# LINEARDriver_DC.net
KiCad netlist of a schematic drawn in Altium Designer
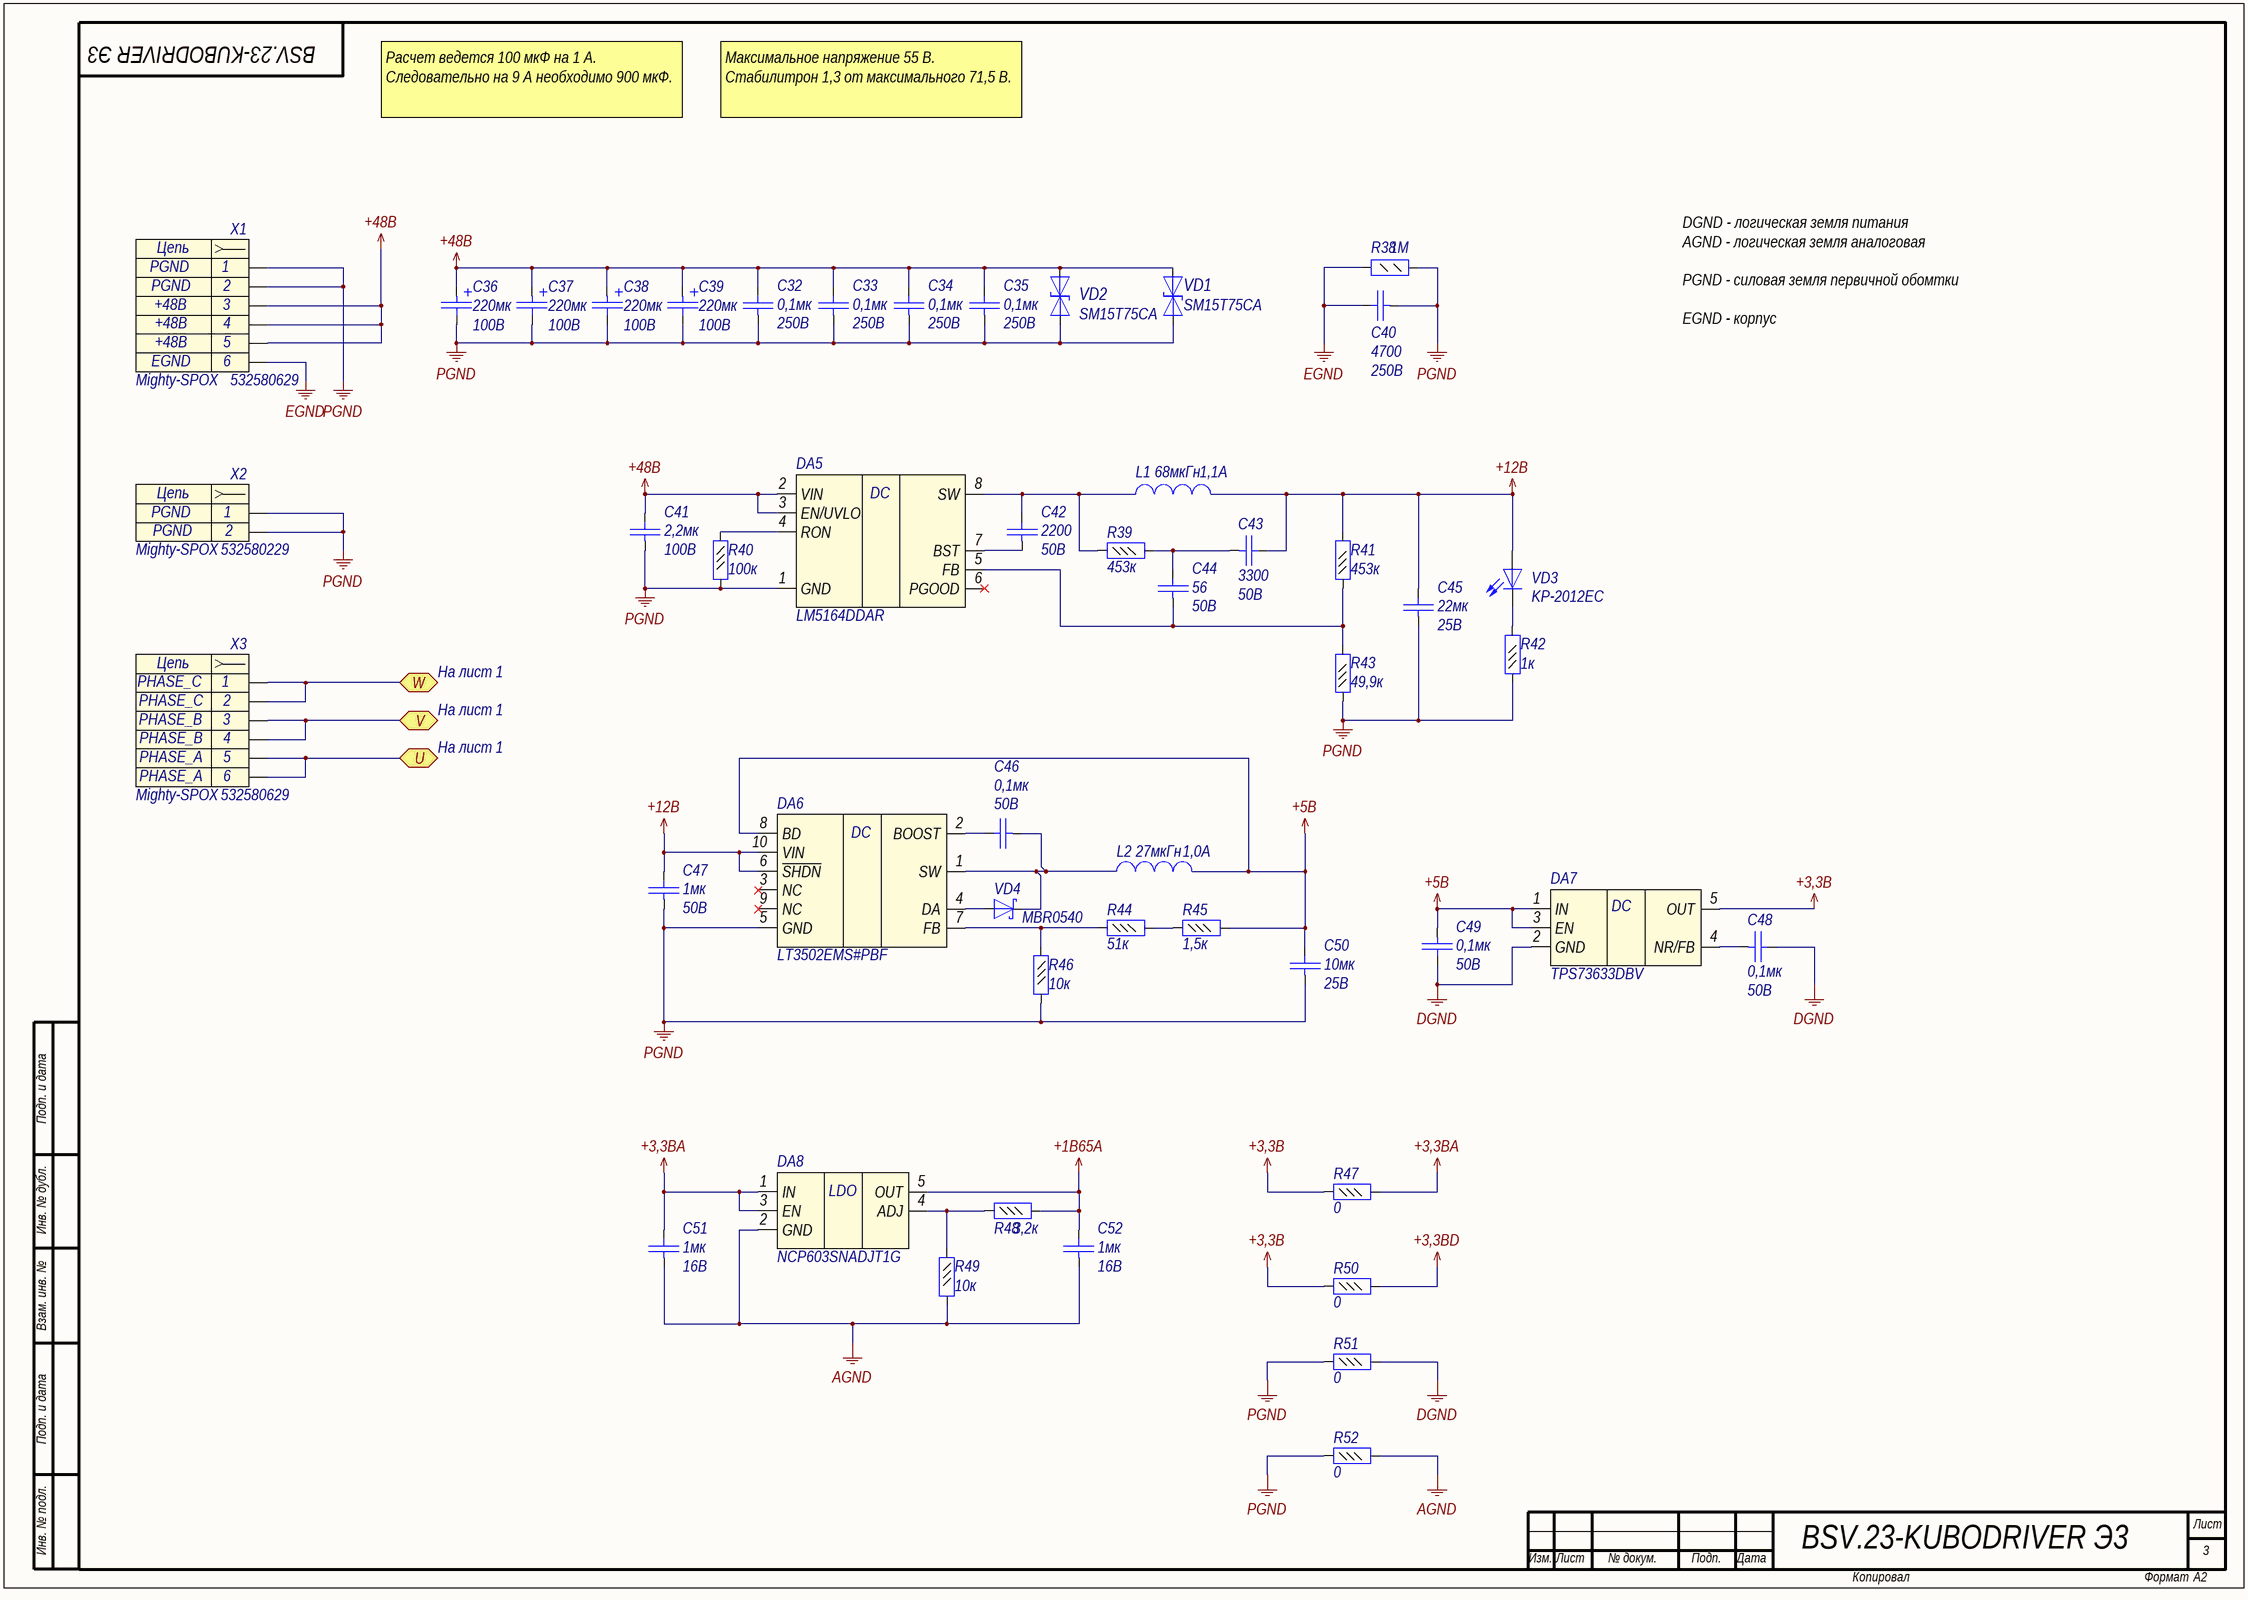
[diagram p0: LINEARDriver_DC.SchDoc]

(export (version "E")
  (design (tool "Eeschema 10.0.6"))
  (components
    (comp (ref "C32")
      (value "0,1мк")
      (footprint "C1206")
      (description "Конденсатор")
      (fields
        (field (name "VOLTAGE") "250В")
        (field (name "PART NUMBER") "GRM31CR72E104K")
        (field (name "Comment") "Capacitor")
      )
      (libsource (lib "MOP44") (part "Capacitor"))
    )
    (comp (ref "C33")
      (value "0,1мк")
      (footprint "C1206")
      (description "Конденсатор")
      (fields
        (field (name "VOLTAGE") "250В")
        (field (name "PART NUMBER") "GRM31CR72E104K")
        (field (name "Comment") "Capacitor")
      )
      (libsource (lib "MOP44") (part "Capacitor"))
    )
    (comp (ref "C34")
      (value "0,1мк")
      (footprint "C1206")
      (description "Конденсатор")
      (fields
        (field (name "VOLTAGE") "250В")
        (field (name "PART NUMBER") "GRM31CR72E104K")
        (field (name "Comment") "Capacitor")
      )
      (libsource (lib "MOP44") (part "Capacitor"))
    )
    (comp (ref "C35")
      (value "0,1мк")
      (footprint "C1206")
      (description "Конденсатор")
      (fields
        (field (name "VOLTAGE") "250В")
        (field (name "PART NUMBER") "GRM31CR72E104K")
        (field (name "Comment") "Capacitor")
      )
      (libsource (lib "MOP44") (part "Capacitor"))
    )
    (comp (ref "C36")
      (value "220мк")
      (footprint "K50-35(12.5X25)_V")
      (description "Конденсатор полярный")
      (fields
        (field (name "VOLTAGE") "100B")
        (field (name "PART NUMBER") "B41851A9227M000")
        (field (name "Comment") "Capacitor_pol")
      )
      (libsource (lib "MOP44") (part "Capacitor_pol"))
    )
    (comp (ref "C37")
      (value "220мк")
      (footprint "K50-35(12.5X25)_V")
      (description "Конденсатор полярный")
      (fields
        (field (name "VOLTAGE") "100B")
        (field (name "PART NUMBER") "B41851A9227M000")
        (field (name "Comment") "Capacitor_pol")
      )
      (libsource (lib "MOP44") (part "Capacitor_pol"))
    )
    (comp (ref "C38")
      (value "220мк")
      (footprint "K50-35(12.5X25)_V")
      (description "Конденсатор полярный")
      (fields
        (field (name "VOLTAGE") "100B")
        (field (name "PART NUMBER") "B41851A9227M000")
        (field (name "Comment") "Capacitor_pol")
      )
      (libsource (lib "MOP44") (part "Capacitor_pol"))
    )
    (comp (ref "C39")
      (value "220мк")
      (footprint "K50-35(12.5X25)_V")
      (description "Конденсатор полярный")
      (fields
        (field (name "VOLTAGE") "100B")
        (field (name "PART NUMBER") "B41851A9227M000")
        (field (name "Comment") "Capacitor_pol")
      )
      (libsource (lib "MOP44") (part "Capacitor_pol"))
    )
    (comp (ref "C40")
      (value "4700")
      (footprint "C0805")
      (description "Конденсатор")
      (fields
        (field (name "VOLTAGE") "250В")
        (field (name "PART NUMBER") "GRM21AR72E472KW")
        (field (name "Comment") "Capacitor")
      )
      (libsource (lib "MOP44") (part "Capacitor"))
    )
    (comp (ref "C41")
      (value "2,2мк")
      (footprint "C1210")
      (description "Конденсатор")
      (fields (field (name "VOLTAGE") "100В") (field (name "PART NUMBER") "GCJ32DR72A225KA01L"))
      (libsource (lib "MOP44") (part "Capacitor"))
    )
    (comp (ref "C42")
      (value "2200")
      (footprint "C0402")
      (description "Конденсатор")
      (fields
        (field (name "VOLTAGE") "50B")
        (field (name "PART NUMBER") "GRM155R71H222K")
        (field (name "Comment") "Capacitor")
      )
      (libsource (lib "MOP44") (part "Capacitor"))
    )
    (comp (ref "C43")
      (value "3300")
      (footprint "C0402")
      (description "Конденсатор")
      (fields
        (field (name "VOLTAGE") "50В")
        (field (name "PART NUMBER") "GRM155R71H332KA01D ")
        (field (name "Comment") "Capacitor")
      )
      (libsource (lib "MOP44") (part "Capacitor"))
    )
    (comp (ref "C44")
      (value "56")
      (footprint "C0402")
      (description "Конденсатор")
      (fields
        (field (name "VOLTAGE") "50B")
        (field (name "PART NUMBER") "GRM1555C1H560J*")
        (field (name "Comment") "Capacitor")
      )
      (libsource (lib "MOP44") (part "Capacitor"))
    )
    (comp (ref "C45")
      (value "22мк")
      (footprint "C1210")
      (description "Конденсатор")
      (fields
        (field (name "VOLTAGE") "25B")
        (field (name "PART NUMBER") "TMK325B7226KMHT")
        (field (name "Comment") "Capacitor")
      )
      (libsource (lib "MOP44") (part "Capacitor"))
    )
    (comp (ref "C46")
      (value "0,1мк")
      (footprint "C0402")
      (description "Конденсатор")
      (fields
        (field (name "VOLTAGE") "50В")
        (field (name "PART NUMBER") "GRM155R71H104KE14D ")
        (field (name "Comment") "Capacitor")
      )
      (libsource (lib "MOP44") (part "Capacitor"))
    )
    (comp (ref "C47")
      (value "1мк")
      (footprint "C0805")
      (description "Конденсатор")
      (fields
        (field (name "VOLTAGE") "50B")
        (field (name "PART NUMBER") "GRM21BR71H105K")
        (field (name "Comment") "Capacitor")
      )
      (libsource (lib "MOP44") (part "Capacitor"))
    )
    (comp (ref "C48")
      (value "0,1мк")
      (footprint "C0402")
      (description "Конденсатор")
      (fields
        (field (name "VOLTAGE") "50В")
        (field (name "PART NUMBER") "GRM155R71H104KE14D ")
        (field (name "Comment") "Capacitor")
      )
      (libsource (lib "MOP44") (part "Capacitor"))
    )
    (comp (ref "C49")
      (value "0,1мк")
      (footprint "C0402")
      (description "Конденсатор")
      (fields
        (field (name "VOLTAGE") "50В")
        (field (name "PART NUMBER") "GRM155R71H104KE14D ")
        (field (name "Comment") "Capacitor")
      )
      (libsource (lib "MOP44") (part "Capacitor"))
    )
    (comp (ref "C50")
      (value "10мк")
      (footprint "C1206")
      (description "Конденсатор")
      (fields
        (field (name "VOLTAGE") "25В")
        (field (name "PART NUMBER") "GRM31CR71E106KA12L*")
        (field (name "Comment") "Capacitor")
      )
      (libsource (lib "MOP44") (part "Capacitor"))
    )
    (comp (ref "C51")
      (value "1мк")
      (footprint "C0603")
      (description "Конденсатор")
      (fields
        (field (name "VOLTAGE") "16B")
        (field (name "PART NUMBER") "GRM188R71C105KA12D**")
        (field (name "Comment") "Capacitor")
      )
      (libsource (lib "MOP44") (part "Capacitor"))
    )
    (comp (ref "C52")
      (value "1мк")
      (footprint "C0603")
      (description "Конденсатор")
      (fields
        (field (name "VOLTAGE") "16B")
        (field (name "PART NUMBER") "GRM188R71C105KA12D**")
        (field (name "Comment") "Capacitor")
      )
      (libsource (lib "MOP44") (part "Capacitor"))
    )
    (comp (ref "DA5")
      (value "LM5164")
      (footprint "SO Powerpad8")
      (description "1-A synchronous buck DC/DC converter with ultra-low IQ")
      (fields (field (name "PART NUMBER") "LM5164DDAR") (field (name "MANUFACTURER") "Texas Instruments"))
      (libsource (lib "MOP44") (part "LM5164"))
    )
    (comp (ref "DA6")
      (value "LT3502_MS")
      (footprint "MSOP10")
      (description "1.1MHz/2.2MHz, 500mA  Step-Down Regulators")
      (fields (field (name "PART NUMBER") "LT3502EMS#PBF") (field (name "MANUFACTURER") "Linear Technology"))
      (libsource (lib "MOP44") (part "LT3502_MS"))
    )
    (comp (ref "DA7")
      (value "TPS736DBV")
      (footprint "SOT23-5")
      (description "400-mA Low-Dropout Regulator with Reverse Current  Protection")
      (fields (field (name "PART NUMBER") "TPS73633DBV") (field (name "MANUFACTURER") "Texas Instruments"))
      (libsource (lib "MOP44") (part "TPS736DBV"))
    )
    (comp (ref "DA8")
      (value "NCP603")
      (footprint "TSOP5")
      (description "High Performance  CMOS LDO Regulator with  Enable and Enhanced ESD  Protection")
      (fields (field (name "PART NUMBER") "NCP603SNADJT1G") (field (name "MANUFACTURER") "ON Semiconductor"))
      (libsource (lib "MOP44") (part "NCP603"))
    )
    (comp (ref "L1")
      (value "68мкГн")
      (footprint "SDR1006")
      (description "EMI Suppression Filter")
      (fields
        (field (name "RATED CURRENT") "1,1A")
        (field (name "PART NUMBER") "SDR1006- 680KL")
        (field (name "Comment") "Inductor")
      )
      (libsource (lib "MOP44") (part "Inductor"))
    )
    (comp (ref "L2")
      (value "27мкГн")
      (footprint "SDR0604")
      (description "EMI Suppression Filter")
      (fields
        (field (name "RATED CURRENT") "1,0A")
        (field (name "PART NUMBER") "SDR0604- 270YL")
        (field (name "Comment") "Inductor")
      )
      (libsource (lib "MOP44") (part "Inductor"))
    )
    (comp (ref "R38")
      (value "1М")
      (footprint "R0805")
      (description "Резистор")
      (fields (field (name "PART NUMBER") "RC0805FR-071ML") (field (name "POWER") "0,125Вт"))
      (libsource (lib "MOP44") (part "Resistor_0,125Вт"))
    )
    (comp (ref "R39")
      (value "453к")
      (footprint "R0402")
      (description "Резистор")
      (fields (field (name "PART NUMBER") "RC0402FR-07453KL") (field (name "POWER") "0,062Вт"))
      (libsource (lib "") (part "Resistor_0,062Вт_1"))
    )
    (comp (ref "R40")
      (value "100к")
      (footprint "R0402")
      (description "Резистор")
      (fields (field (name "PART NUMBER") "RC0402FR-07100KL") (field (name "POWER") "0,062Вт"))
      (libsource (lib "") (part "Resistor_0,062Вт_2"))
    )
    (comp (ref "R41")
      (value "453к")
      (footprint "R0402")
      (description "Резистор")
      (fields (field (name "PART NUMBER") "RC0402FR-07453KL") (field (name "POWER") "0,062Вт"))
      (libsource (lib "MOP44") (part "Resistor_0,062Вт"))
    )
    (comp (ref "R42")
      (value "1к")
      (footprint "R0402")
      (description "Резистор")
      (fields (field (name "PART NUMBER") "RC0402FR-071KL") (field (name "POWER") "0,062Вт"))
      (libsource (lib "MOP44") (part "Resistor_0,062Вт"))
    )
    (comp (ref "R43")
      (value "49,9к")
      (footprint "R0402")
      (description "Резистор")
      (fields (field (name "PART NUMBER") "RC0402FR-0749K9L") (field (name "POWER") "0,062Вт"))
      (libsource (lib "MOP44") (part "Resistor_0,062Вт"))
    )
    (comp (ref "R44")
      (value "51к")
      (footprint "R0402")
      (description "Резистор")
      (fields (field (name "PART NUMBER") "RC0402FR-0751KL") (field (name "POWER") "0,062Вт"))
      (libsource (lib "") (part "Resistor_0,062Вт_1"))
    )
    (comp (ref "R45")
      (value "1,5к")
      (footprint "R0402")
      (description "Резистор")
      (fields (field (name "PART NUMBER") "RC0402FR-071K5") (field (name "POWER") "0,062Вт"))
      (libsource (lib "") (part "Resistor_0,062Вт_1"))
    )
    (comp (ref "R46")
      (value "10к")
      (footprint "R0402")
      (description "Резистор")
      (fields (field (name "PART NUMBER") "RC0402FR-0710KL") (field (name "POWER") "0,062Вт"))
      (libsource (lib "") (part "Resistor_0,062Вт_2"))
    )
    (comp (ref "R47")
      (value "0")
      (footprint "R0603")
      (description "Резистор")
      (fields (field (name "PART NUMBER") "RC0603FR-070RL") (field (name "POWER") "0,062Вт"))
      (libsource (lib "") (part "Resistor_0,062Вт_1"))
    )
    (comp (ref "R48")
      (value "3,2к")
      (footprint "R0402")
      (description "Резистор")
      (fields (field (name "PART NUMBER") "RT0402BRD073K2L") (field (name "POWER") "0,062Вт"))
      (libsource (lib "") (part "Resistor_0,062Вт_1"))
    )
    (comp (ref "R49")
      (value "10к")
      (footprint "R0402")
      (description "Резистор")
      (fields (field (name "PART NUMBER") "RC0402FR-0710KL") (field (name "POWER") "0,062Вт"))
      (libsource (lib "") (part "Resistor_0,062Вт_2"))
    )
    (comp (ref "R50")
      (value "0")
      (footprint "R0603")
      (description "Резистор")
      (fields (field (name "PART NUMBER") "RC0603FR-070RL") (field (name "POWER") "0,062Вт"))
      (libsource (lib "") (part "Resistor_0,062Вт_1"))
    )
    (comp (ref "R51")
      (value "0")
      (footprint "R0603")
      (description "Резистор")
      (fields (field (name "PART NUMBER") "RC0603FR-070RL") (field (name "POWER") "0,062Вт"))
      (libsource (lib "") (part "Resistor_0,062Вт_1"))
    )
    (comp (ref "R52")
      (value "0")
      (footprint "R0603")
      (description "Резистор")
      (fields (field (name "PART NUMBER") "RC0603FR-070RL") (field (name "POWER") "0,062Вт"))
      (libsource (lib "") (part "Resistor_0,062Вт_1"))
    )
    (comp (ref "VD1")
      (value "DiodeZenerDual")
      (footprint "SMC")
      (description "Cтабилитрон (диод выпрямительный лавинный) двусторонний")
      (fields (field (name "PART NUMBER") "SM15T75CA"))
      (libsource (lib "MOP44") (part "DiodeZenerDual"))
    )
    (comp (ref "VD2")
      (value "DiodeZenerDual")
      (footprint "SMC")
      (description "Cтабилитрон (диод выпрямительный лавинный) двусторонний")
      (fields (field (name "PART NUMBER") "SM15T75CA"))
      (libsource (lib "MOP44") (part "DiodeZenerDual"))
    )
    (comp (ref "VD3")
      (value "LED")
      (footprint "L_0805")
      (description "Светодиод")
      (fields (field (name "PART NUMBER") "KP-2012EC"))
      (libsource (lib "MOP44") (part "LED"))
    )
    (comp (ref "VD4")
      (value "DiodeSchottky")
      (footprint "SOD-123")
      (description "Диод Шоттки")
      (fields (field (name "PART NUMBER") "MBR0540"))
      (libsource (lib "MOP44") (part "DiodeSchottky"))
    )
    (comp (ref "X1")
      (value "Header_6_sct")
      (footprint "MOLEX_532580629")
      (description "Разъем - 6 конт. розетка")
      (fields (field (name "PART NAME") "Mighty-SPOX") (field (name "PART NUMBER") "532580629"))
      (libsource (lib "MOP44") (part "Header_6_sct"))
    )
    (comp (ref "X2")
      (value "Header_2_sct")
      (footprint "MOLEX_532580229")
      (description "Разъем - 2 конт. розетка")
      (fields (field (name "PART NAME") "Mighty-SPOX") (field (name "PART NUMBER") "532580229"))
      (libsource (lib "MOP44") (part "Header_2_sct"))
    )
    (comp (ref "X3")
      (value "Header_6_sct")
      (footprint "MOLEX_532580629")
      (description "Разъем - 6 конт. розетка")
      (fields (field (name "PART NAME") "Mighty-SPOX") (field (name "PART NUMBER") "532580629"))
      (libsource (lib "MOP44") (part "Header_6_sct"))
    )
  )
  (nets
    (net (code "1") (name "+1B65A") (class "Default")
      (node (ref "C52") (pin "2") (pinfunction "2_2") (pintype "passive"))
      (node (ref "DA8") (pin "5") (pinfunction "OUT_5") (pintype "power_in"))
      (node (ref "R48") (pin "2") (pinfunction "2_2") (pintype "passive"))
    )
    (net (code "2") (name "+3,3B") (class "Default")
      (node (ref "DA7") (pin "5") (pinfunction "OUT_5") (pintype "power_in"))
      (node (ref "R47") (pin "1") (pinfunction "1_1") (pintype "passive"))
      (node (ref "R50") (pin "1") (pinfunction "1_1") (pintype "passive"))
    )
    (net (code "3") (name "+3,3BA") (class "Default")
      (node (ref "C51") (pin "2") (pinfunction "2_2") (pintype "passive"))
      (node (ref "DA8") (pin "1") (pinfunction "IN_1") (pintype "power_in"))
      (node (ref "DA8") (pin "3") (pinfunction "EN_3") (pintype "power_in"))
      (node (ref "R47") (pin "2") (pinfunction "2_2") (pintype "passive"))
    )
    (net (code "4") (name "+3,3BD") (class "Default")
      (node (ref "R50") (pin "2") (pinfunction "2_2") (pintype "passive"))
    )
    (net (code "5") (name "+5B") (class "Default")
      (node (ref "C49") (pin "1") (pinfunction "1_1") (pintype "passive"))
      (node (ref "C50") (pin "2") (pinfunction "2_2") (pintype "passive"))
      (node (ref "DA6") (pin "8") (pinfunction "BD_8") (pintype "power_in"))
      (node (ref "DA7") (pin "1") (pinfunction "IN_1") (pintype "power_in"))
      (node (ref "DA7") (pin "3") (pinfunction "EN_3") (pintype "power_in"))
      (node (ref "L2") (pin "2") (pinfunction "2_2") (pintype "passive"))
      (node (ref "R45") (pin "2") (pinfunction "2_2") (pintype "passive"))
    )
    (net (code "6") (name "+12B") (class "Default")
      (node (ref "C43") (pin "2") (pinfunction "2_2") (pintype "passive"))
      (node (ref "C45") (pin "2") (pinfunction "2_2") (pintype "passive"))
      (node (ref "C47") (pin "2") (pinfunction "2_2") (pintype "passive"))
      (node (ref "DA6") (pin "10") (pinfunction "VIN_10") (pintype "power_in"))
      (node (ref "DA6") (pin "6") (pinfunction "~{SHDN}_6") (pintype "power_in"))
      (node (ref "L1") (pin "2") (pinfunction "2_2") (pintype "passive"))
      (node (ref "R41") (pin "2") (pinfunction "2_2") (pintype "passive"))
      (node (ref "VD3") (pin "2") (pinfunction "A_2") (pintype "passive"))
    )
    (net (code "7") (name "+48B") (class "Default")
      (node (ref "C32") (pin "2") (pinfunction "2_2") (pintype "passive"))
      (node (ref "C33") (pin "2") (pinfunction "2_2") (pintype "passive"))
      (node (ref "C34") (pin "2") (pinfunction "2_2") (pintype "passive"))
      (node (ref "C35") (pin "2") (pinfunction "2_2") (pintype "passive"))
      (node (ref "C36") (pin "1") (pinfunction "1_1") (pintype "passive"))
      (node (ref "C37") (pin "1") (pinfunction "1_1") (pintype "passive"))
      (node (ref "C38") (pin "1") (pinfunction "1_1") (pintype "passive"))
      (node (ref "C39") (pin "1") (pinfunction "1_1") (pintype "passive"))
      (node (ref "C41") (pin "2") (pinfunction "2_2") (pintype "passive"))
      (node (ref "DA5") (pin "2") (pinfunction "VIN_2") (pintype "power_in"))
      (node (ref "DA5") (pin "3") (pinfunction "EN/UVLO_3") (pintype "power_in"))
      (node (ref "VD1") (pin "1") (pinfunction "K_1") (pintype "passive"))
      (node (ref "VD2") (pin "2") (pinfunction "A_2") (pintype "passive"))
      (node (ref "X1") (pin "3") (pinfunction "3_3") (pintype "passive"))
      (node (ref "X1") (pin "4") (pinfunction "4_4") (pintype "passive"))
      (node (ref "X1") (pin "5") (pinfunction "5_5") (pintype "passive"))
    )
    (net (code "8") (name "/U") (class "Default")
      (node (ref "X3") (pin "5") (pinfunction "5_5") (pintype "passive"))
      (node (ref "X3") (pin "6") (pinfunction "6_6") (pintype "passive"))
    )
    (net (code "9") (name "/V") (class "Default")
      (node (ref "X3") (pin "3") (pinfunction "3_3") (pintype "passive"))
      (node (ref "X3") (pin "4") (pinfunction "4_4") (pintype "passive"))
    )
    (net (code "10") (name "/W") (class "Default")
      (node (ref "X3") (pin "1") (pinfunction "1_1") (pintype "passive"))
      (node (ref "X3") (pin "2") (pinfunction "2_2") (pintype "passive"))
    )
    (net (code "11") (name "AGND") (class "Default")
      (node (ref "C51") (pin "1") (pinfunction "1_1") (pintype "passive"))
      (node (ref "C52") (pin "1") (pinfunction "1_1") (pintype "passive"))
      (node (ref "DA8") (pin "2") (pinfunction "GND_2") (pintype "power_in"))
      (node (ref "R49") (pin "2") (pinfunction "2_2") (pintype "passive"))
      (node (ref "R52") (pin "2") (pinfunction "2_2") (pintype "passive"))
    )
    (net (code "12") (name "DGND") (class "Default")
      (node (ref "C48") (pin "2") (pinfunction "2_2") (pintype "passive"))
      (node (ref "C49") (pin "2") (pinfunction "2_2") (pintype "passive"))
      (node (ref "DA7") (pin "2") (pinfunction "GND_2") (pintype "power_in"))
      (node (ref "R51") (pin "2") (pinfunction "2_2") (pintype "passive"))
    )
    (net (code "13") (name "EGND") (class "Default")
      (node (ref "C40") (pin "2") (pinfunction "2_2") (pintype "passive"))
      (node (ref "R38") (pin "2") (pinfunction "2_2") (pintype "passive"))
      (node (ref "X1") (pin "6") (pinfunction "6_6") (pintype "passive"))
    )
    (net (code "14") (name "Net-(C43-Pad1)") (class "Default")
      (node (ref "C43") (pin "1") (pinfunction "1_1") (pintype "passive"))
      (node (ref "C44") (pin "2") (pinfunction "2_2") (pintype "passive"))
      (node (ref "R39") (pin "2") (pinfunction "2_2") (pintype "passive"))
    )
    (net (code "15") (name "Net-(DA5-BST)") (class "Default")
      (node (ref "C42") (pin "1") (pinfunction "1_1") (pintype "passive"))
      (node (ref "DA5") (pin "7") (pinfunction "BST_7") (pintype "power_in"))
    )
    (net (code "16") (name "Net-(DA5-FB)") (class "Default")
      (node (ref "C44") (pin "1") (pinfunction "1_1") (pintype "passive"))
      (node (ref "DA5") (pin "5") (pinfunction "FB_5") (pintype "power_in"))
      (node (ref "R41") (pin "1") (pinfunction "1_1") (pintype "passive"))
      (node (ref "R43") (pin "2") (pinfunction "2_2") (pintype "passive"))
    )
    (net (code "17") (name "Net-(DA5-RON)") (class "Default")
      (node (ref "DA5") (pin "4") (pinfunction "RON_4") (pintype "power_in"))
      (node (ref "R40") (pin "1") (pinfunction "1_1") (pintype "passive"))
    )
    (net (code "18") (name "Net-(DA5-SW)") (class "Default")
      (node (ref "C42") (pin "2") (pinfunction "2_2") (pintype "passive"))
      (node (ref "DA5") (pin "8") (pinfunction "SW_8") (pintype "power_in"))
      (node (ref "L1") (pin "1") (pinfunction "1_1") (pintype "passive"))
      (node (ref "R39") (pin "1") (pinfunction "1_1") (pintype "passive"))
    )
    (net (code "19") (name "Net-(DA6-BOOST)") (class "Default")
      (node (ref "C46") (pin "2") (pinfunction "2_2") (pintype "passive"))
      (node (ref "DA6") (pin "2") (pinfunction "BOOST_2") (pintype "power_in"))
    )
    (net (code "20") (name "Net-(DA6-DA)") (class "Default")
      (node (ref "DA6") (pin "4") (pinfunction "DA_4") (pintype "power_in"))
      (node (ref "VD4") (pin "2") (pinfunction "A_2") (pintype "passive"))
    )
    (net (code "21") (name "Net-(DA6-FB)") (class "Default")
      (node (ref "DA6") (pin "7") (pinfunction "FB_7") (pintype "power_in"))
      (node (ref "R44") (pin "1") (pinfunction "1_1") (pintype "passive"))
      (node (ref "R46") (pin "1") (pinfunction "1_1") (pintype "passive"))
    )
    (net (code "22") (name "Net-(DA6-SW)") (class "Default")
      (node (ref "C46") (pin "1") (pinfunction "1_1") (pintype "passive"))
      (node (ref "DA6") (pin "1") (pinfunction "SW_1") (pintype "power_in"))
      (node (ref "L2") (pin "1") (pinfunction "1_1") (pintype "passive"))
      (node (ref "VD4") (pin "1") (pinfunction "K_1") (pintype "passive"))
    )
    (net (code "23") (name "Net-(DA7-NR{slash}FB)") (class "Default")
      (node (ref "C48") (pin "1") (pinfunction "1_1") (pintype "passive"))
      (node (ref "DA7") (pin "4") (pinfunction "NR/FB_4") (pintype "power_in"))
    )
    (net (code "24") (name "Net-(DA8-ADJ)") (class "Default")
      (node (ref "DA8") (pin "4") (pinfunction "ADJ_4") (pintype "power_in"))
      (node (ref "R48") (pin "1") (pinfunction "1_1") (pintype "passive"))
      (node (ref "R49") (pin "1") (pinfunction "1_1") (pintype "passive"))
    )
    (net (code "25") (name "Net-(R44-Pad2)") (class "Default")
      (node (ref "R44") (pin "2") (pinfunction "2_2") (pintype "passive"))
      (node (ref "R45") (pin "1") (pinfunction "1_1") (pintype "passive"))
    )
    (net (code "26") (name "Net-(VD3-K)") (class "Default")
      (node (ref "R42") (pin "2") (pinfunction "2_2") (pintype "passive"))
      (node (ref "VD3") (pin "1") (pinfunction "K_1") (pintype "passive"))
    )
    (net (code "27") (name "PGND") (class "Default")
      (node (ref "C32") (pin "1") (pinfunction "1_1") (pintype "passive"))
      (node (ref "C33") (pin "1") (pinfunction "1_1") (pintype "passive"))
      (node (ref "C34") (pin "1") (pinfunction "1_1") (pintype "passive"))
      (node (ref "C35") (pin "1") (pinfunction "1_1") (pintype "passive"))
      (node (ref "C36") (pin "2") (pinfunction "2_2") (pintype "passive"))
      (node (ref "C37") (pin "2") (pinfunction "2_2") (pintype "passive"))
      (node (ref "C38") (pin "2") (pinfunction "2_2") (pintype "passive"))
      (node (ref "C39") (pin "2") (pinfunction "2_2") (pintype "passive"))
      (node (ref "C40") (pin "1") (pinfunction "1_1") (pintype "passive"))
      (node (ref "C41") (pin "1") (pinfunction "1_1") (pintype "passive"))
      (node (ref "C45") (pin "1") (pinfunction "1_1") (pintype "passive"))
      (node (ref "C47") (pin "1") (pinfunction "1_1") (pintype "passive"))
      (node (ref "C50") (pin "1") (pinfunction "1_1") (pintype "passive"))
      (node (ref "DA5") (pin "1") (pinfunction "GND_1") (pintype "power_in"))
      (node (ref "DA6") (pin "5") (pinfunction "GND_5") (pintype "power_in"))
      (node (ref "R38") (pin "1") (pinfunction "1_1") (pintype "passive"))
      (node (ref "R40") (pin "2") (pinfunction "2_2") (pintype "passive"))
      (node (ref "R42") (pin "1") (pinfunction "1_1") (pintype "passive"))
      (node (ref "R43") (pin "1") (pinfunction "1_1") (pintype "passive"))
      (node (ref "R46") (pin "2") (pinfunction "2_2") (pintype "passive"))
      (node (ref "R51") (pin "1") (pinfunction "1_1") (pintype "passive"))
      (node (ref "R52") (pin "1") (pinfunction "1_1") (pintype "passive"))
      (node (ref "VD1") (pin "2") (pinfunction "A_2") (pintype "passive"))
      (node (ref "VD2") (pin "1") (pinfunction "K_1") (pintype "passive"))
      (node (ref "X1") (pin "1") (pinfunction "1_1") (pintype "passive"))
      (node (ref "X1") (pin "2") (pinfunction "2_2") (pintype "passive"))
      (node (ref "X2") (pin "1") (pinfunction "1_1") (pintype "passive"))
      (node (ref "X2") (pin "2") (pinfunction "2_2") (pintype "passive"))
    )
    (net (code "28") (name "unconnected-(DA5-PGOOD-Pad6)") (class "Default")
      (node (ref "DA5") (pin "6") (pinfunction "PGOOD_6") (pintype "power_in+no_connect"))
    )
    (net (code "29") (name "unconnected-(DA6-NC-Pad3)") (class "Default")
      (node (ref "DA6") (pin "3") (pinfunction "NC_3") (pintype "power_in+no_connect"))
    )
    (net (code "30") (name "unconnected-(DA6-NC-Pad9)") (class "Default")
      (node (ref "DA6") (pin "9") (pinfunction "NC_9") (pintype "power_in+no_connect"))
    )
  )
)
